# furballv3.net
KiCad netlist of a schematic drawn in EAGLE
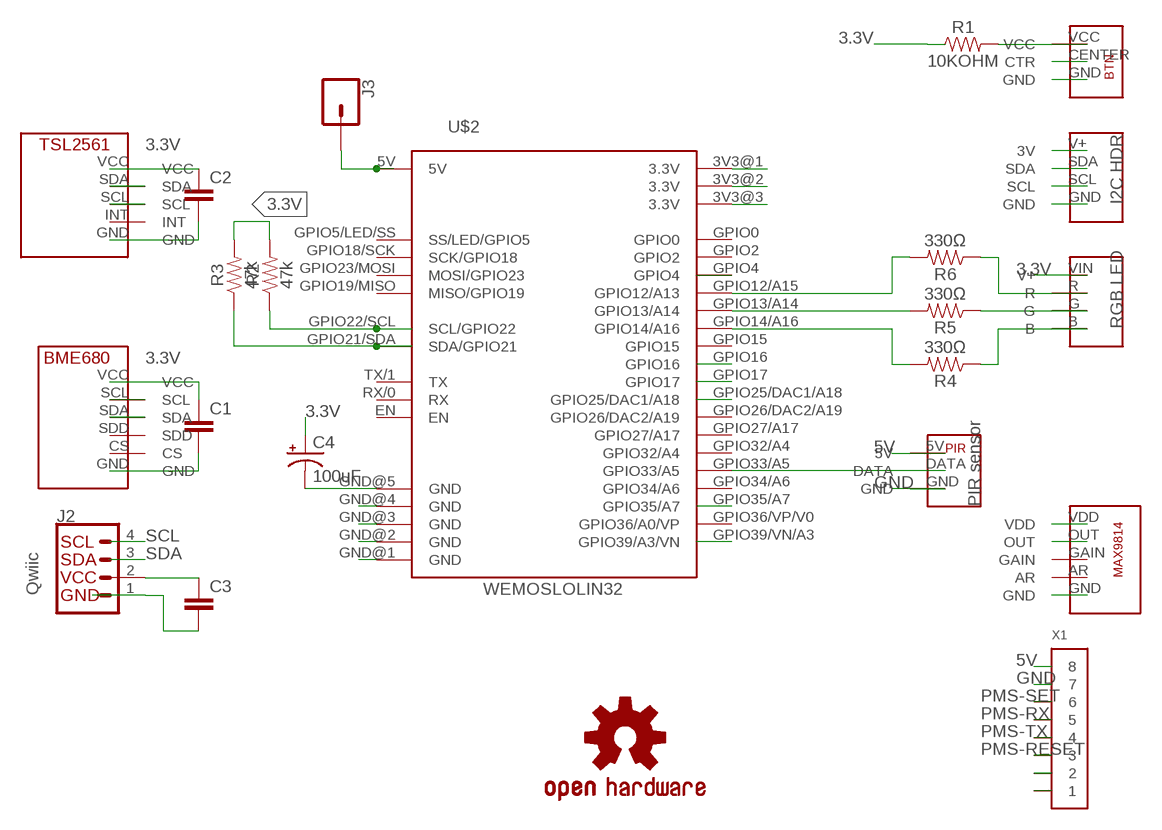
[diagram p0: schematic, sheet 1]

(export (version "E")
  (design (tool "Eeschema 10.0.6"))
  (components
    (comp (ref "C1")
      (value "10pF")
      (footprint "eagle-import:CAP-PTH-SMALL2")
      (libsource (lib "eagle-import") (part "CAPPTH2"))
    )
    (comp (ref "C2")
      (value "10pF")
      (footprint "eagle-import:CAP-PTH-SMALL2")
      (libsource (lib "eagle-import") (part "CAPPTH2"))
    )
    (comp (ref "C3")
      (value "10pF")
      (footprint "eagle-import:CAP-PTH-SMALL2")
      (libsource (lib "eagle-import") (part "CAPPTH2"))
    )
    (comp (ref "C4")
      (value "100uF")
      (footprint "eagle-import:CPOL-RADIAL-2.5MM-6.5MM")
      (libsource (lib "eagle-import") (part "100UF-POLAR-RADIAL-2.5MM-25V-20%"))
    )
    (comp (ref "J2")
      (value "QWIIC_CONNECTORJS-1MM")
      (footprint "eagle-import:1X04_1MM_RA")
      (libsource (lib "eagle-import") (part "QWIIC_CONNECTORJS-1MM"))
    )
    (comp (ref "J3")
      (value "CONN_01")
      (footprint "eagle-import:1X01")
      (libsource (lib "eagle-import") (part "CONN_01"))
    )
    (comp (ref "LOGO1")
      (value "OSHW-LOGOL")
      (footprint "eagle-import:OSHW-LOGO-L")
      (libsource (lib "eagle-import") (part "OSHW-LOGOL"))
    )
    (comp (ref "R1")
      (value "10KOHM")
      (footprint "eagle-import:AXIAL-0.3-KIT")
      (libsource (lib "eagle-import") (part "47KOHM"))
    )
    (comp (ref "R2")
      (value "47k")
      (footprint "eagle-import:AXIAL-0.3")
      (libsource (lib "eagle-import") (part "100KOHM-HORIZ-1/4W-1%"))
    )
    (comp (ref "R3")
      (value "47k")
      (footprint "eagle-import:AXIAL-0.3")
      (libsource (lib "eagle-import") (part "100KOHM-HORIZ-1/4W-1%"))
    )
    (comp (ref "R4")
      (value "330Ω")
      (footprint "eagle-import:AXIAL-0.3")
      (libsource (lib "eagle-import") (part "100KOHM-HORIZ-1/4W-1%"))
    )
    (comp (ref "R5")
      (value "330Ω")
      (footprint "eagle-import:AXIAL-0.3")
      (libsource (lib "eagle-import") (part "100KOHM-HORIZ-1/4W-1%"))
    )
    (comp (ref "R6")
      (value "330Ω")
      (footprint "eagle-import:AXIAL-0.3")
      (libsource (lib "eagle-import") (part "100KOHM-HORIZ-1/4W-1%"))
    )
    (comp (ref "U$1")
      (value "PIRHEADER")
      (footprint "eagle-import:PIRHEADER")
      (libsource (lib "eagle-import") (part "PIRHEADER"))
    )
    (comp (ref "U$2")
      (value "WEMOSLOLIN32")
      (footprint "eagle-import:LOLIN32VAR1")
      (libsource (lib "eagle-import") (part "WEMOSLOLIN32"))
    )
    (comp (ref "U$3")
      (value "BME680BREAKOUT")
      (footprint "eagle-import:BME680BREAKOUT")
      (libsource (lib "eagle-import") (part "BME680BREAKOUT"))
    )
    (comp (ref "U$4")
      (value "TSL2561BREAKOUT")
      (footprint "eagle-import:TSL2561BREAKOUT")
      (libsource (lib "eagle-import") (part "TSL2561BREAKOUT"))
    )
    (comp (ref "U$5")
      (value "RGBLEDHEADER")
      (footprint "eagle-import:RGBLEDHDR")
      (libsource (lib "eagle-import") (part "RGBLEDHEADER"))
    )
    (comp (ref "U$6")
      (value "I2CHEADER")
      (footprint "eagle-import:I2CHEADER")
      (libsource (lib "eagle-import") (part "I2CHEADER"))
    )
    (comp (ref "U$7")
      (value "MAX9814BREAKOUT")
      (footprint "eagle-import:MAX9814BREAKOUT")
      (libsource (lib "eagle-import") (part "MAX9814BREAKOUT"))
    )
    (comp (ref "U$8")
      (value "PUSHBUTTONHEADER")
      (footprint "eagle-import:PUSHBUTTONHEADER")
      (libsource (lib "eagle-import") (part "PUSHBUTTONHEADER"))
    )
    (comp (ref "X1")
      (value "CONN_8-1-53261")
      (footprint "eagle-import:PB-53261-08")
      (libsource (lib "eagle-import") (part "CONN_8-1-53261"))
    )
  )
  (nets
    (net (code "1") (name "/5V") (class "Default")
      (node (ref "J3") (pin "1") (pinfunction "1_1") (pintype "passive"))
      (node (ref "U$1") (pin "5V") (pinfunction "5V_5V") (pintype "power_in"))
      (node (ref "U$2") (pin "5V") (pinfunction "5V_5V") (pintype "power_in"))
      (node (ref "X1") (pin "8") (pinfunction "8_8") (pintype "bidirectional"))
    )
    (net (code "2") (name "/BUTTON") (class "Default")
      (node (ref "U$2") (pin "GPIO35/A7") (pinfunction "GPIO35/A7_GPIO35/A7") (pintype "bidirectional"))
      (node (ref "U$8") (pin "CENTER") (pinfunction "CTR_CENTER") (pintype "bidirectional"))
    )
    (net (code "3") (name "/GND") (class "Default")
      (node (ref "C1") (pin "2") (pinfunction "2_2") (pintype "passive"))
      (node (ref "C2") (pin "2") (pinfunction "2_2") (pintype "passive"))
      (node (ref "C3") (pin "2") (pinfunction "2_2") (pintype "passive"))
      (node (ref "C4") (pin "2") (pinfunction "-_2") (pintype "passive"))
      (node (ref "J2") (pin "1") (pinfunction "GND_1") (pintype "power_in"))
      (node (ref "U$1") (pin "GND") (pinfunction "GND_GND") (pintype "power_in"))
      (node (ref "U$2") (pin "GND@1") (pinfunction "GND_GND@1") (pintype "power_in"))
      (node (ref "U$2") (pin "GND@2") (pinfunction "GND_GND@2") (pintype "bidirectional"))
      (node (ref "U$2") (pin "GND@3") (pinfunction "GND_GND@3") (pintype "bidirectional"))
      (node (ref "U$2") (pin "GND@4") (pinfunction "GND_GND@4") (pintype "bidirectional"))
      (node (ref "U$2") (pin "GND@5") (pinfunction "GND_GND@5") (pintype "bidirectional"))
      (node (ref "U$3") (pin "GND") (pinfunction "GND_GND") (pintype "power_in"))
      (node (ref "U$4") (pin "GND") (pinfunction "GND_GND") (pintype "power_in"))
      (node (ref "U$6") (pin "GND") (pinfunction "GND_GND") (pintype "power_in"))
      (node (ref "U$7") (pin "GND") (pinfunction "GND_GND") (pintype "power_in"))
      (node (ref "U$8") (pin "GND") (pinfunction "GND_GND") (pintype "power_in"))
      (node (ref "X1") (pin "7") (pinfunction "7_7") (pintype "bidirectional"))
    )
    (net (code "4") (name "/PMS-RESET") (class "Default")
      (node (ref "U$2") (pin "GPIO25/DAC1/A18") (pinfunction "GPIO25/DAC1/A18_GPIO25/DAC1/A18") (pintype "bidirectional"))
      (node (ref "X1") (pin "3") (pinfunction "3_3") (pintype "bidirectional"))
    )
    (net (code "5") (name "/PMS-RX") (class "Default")
      (node (ref "U$2") (pin "GPIO16") (pinfunction "GPIO16_GPIO16") (pintype "bidirectional"))
      (node (ref "X1") (pin "5") (pinfunction "5_5") (pintype "bidirectional"))
    )
    (net (code "6") (name "/PMS-SET") (class "Default")
      (node (ref "U$2") (pin "GPIO4") (pinfunction "GPIO4_GPIO4") (pintype "bidirectional"))
      (node (ref "X1") (pin "6") (pinfunction "6_6") (pintype "bidirectional"))
    )
    (net (code "7") (name "/PMS-TX") (class "Default")
      (node (ref "U$2") (pin "GPIO17") (pinfunction "GPIO17_GPIO17") (pintype "bidirectional"))
      (node (ref "X1") (pin "4") (pinfunction "4_4") (pintype "bidirectional"))
    )
    (net (code "8") (name "/SCL") (class "Default")
      (node (ref "J2") (pin "4") (pinfunction "SCL_4") (pintype "passive"))
      (node (ref "R2") (pin "P$1") (pinfunction "1_P$1") (pintype "passive"))
      (node (ref "U$2") (pin "GPIO22/SCL") (pinfunction "SCL/GPIO22_GPIO22/SCL") (pintype "bidirectional"))
      (node (ref "U$3") (pin "SCL") (pinfunction "SCL_SCL") (pintype "bidirectional"))
      (node (ref "U$4") (pin "SCL") (pinfunction "SCL_SCL") (pintype "bidirectional"))
      (node (ref "U$6") (pin "SCL") (pinfunction "SCL_SCL") (pintype "bidirectional"))
    )
    (net (code "9") (name "/SDA") (class "Default")
      (node (ref "J2") (pin "3") (pinfunction "SDA_3") (pintype "passive"))
      (node (ref "R3") (pin "P$1") (pinfunction "1_P$1") (pintype "passive"))
      (node (ref "U$2") (pin "GPIO21/SDA") (pinfunction "SDA/GPIO21_GPIO21/SDA") (pintype "bidirectional"))
      (node (ref "U$3") (pin "SDA") (pinfunction "SDA_SDA") (pintype "bidirectional"))
      (node (ref "U$4") (pin "SDA") (pinfunction "SDA_SDA") (pintype "bidirectional"))
      (node (ref "U$6") (pin "SDA") (pinfunction "SDA_SDA") (pintype "bidirectional"))
    )
    (net (code "10") (name "/SOUND") (class "Default")
      (node (ref "U$2") (pin "GPIO39/VN/A3") (pinfunction "GPIO39/A3/VN_GPIO39/VN/A3") (pintype "bidirectional"))
      (node (ref "U$7") (pin "OUT") (pinfunction "OUT_OUT") (pintype "output"))
    )
    (net (code "11") (name "3.3V") (class "Default")
      (node (ref "C1") (pin "1") (pinfunction "1_1") (pintype "passive"))
      (node (ref "C2") (pin "1") (pinfunction "1_1") (pintype "passive"))
      (node (ref "C3") (pin "1") (pinfunction "1_1") (pintype "passive"))
      (node (ref "C4") (pin "1") (pinfunction "+_1") (pintype "passive"))
      (node (ref "J2") (pin "2") (pinfunction "VCC_2") (pintype "power_in"))
      (node (ref "R1") (pin "P$1") (pinfunction "1_P$1") (pintype "passive"))
      (node (ref "R2") (pin "P$2") (pinfunction "2_P$2") (pintype "passive"))
      (node (ref "R3") (pin "P$2") (pinfunction "2_P$2") (pintype "passive"))
      (node (ref "U$2") (pin "3V3@1") (pinfunction "3.3V_3V3@1") (pintype "bidirectional"))
      (node (ref "U$2") (pin "3V3@2") (pinfunction "3.3V_3V3@2") (pintype "bidirectional"))
      (node (ref "U$2") (pin "3V3@3") (pinfunction "3.3V_3V3@3") (pintype "power_in"))
      (node (ref "U$3") (pin "VCC") (pinfunction "VCC_VCC") (pintype "power_in"))
      (node (ref "U$4") (pin "VCC") (pinfunction "VCC_VCC") (pintype "power_in"))
      (node (ref "U$5") (pin "VIN") (pinfunction "V+_VIN") (pintype "power_in"))
      (node (ref "U$6") (pin "V+") (pinfunction "3V_V+") (pintype "power_in"))
      (node (ref "U$7") (pin "VDD") (pinfunction "VDD_VDD") (pintype "power_in"))
    )
    (net (code "12") (name "Net-(R1-2)") (class "Default")
      (node (ref "R1") (pin "P$2") (pinfunction "2_P$2") (pintype "passive"))
      (node (ref "U$8") (pin "VCC") (pinfunction "VCC_VCC") (pintype "bidirectional"))
    )
    (net (code "13") (name "Net-(R4-1)") (class "Default")
      (node (ref "R4") (pin "P$1") (pinfunction "1_P$1") (pintype "passive"))
      (node (ref "U$5") (pin "B") (pinfunction "B_B") (pintype "input"))
    )
    (net (code "14") (name "Net-(R4-2)") (class "Default")
      (node (ref "R4") (pin "P$2") (pinfunction "2_P$2") (pintype "passive"))
      (node (ref "U$2") (pin "GPIO14/A16") (pinfunction "GPIO14/A16_GPIO14/A16") (pintype "bidirectional"))
    )
    (net (code "15") (name "Net-(R5-1)") (class "Default")
      (node (ref "R5") (pin "P$1") (pinfunction "1_P$1") (pintype "passive"))
      (node (ref "U$5") (pin "G") (pinfunction "G_G") (pintype "input"))
    )
    (net (code "16") (name "Net-(R5-2)") (class "Default")
      (node (ref "R5") (pin "P$2") (pinfunction "2_P$2") (pintype "passive"))
      (node (ref "U$2") (pin "GPIO13/A14") (pinfunction "GPIO13/A14_GPIO13/A14") (pintype "bidirectional"))
    )
    (net (code "17") (name "Net-(R6-1)") (class "Default")
      (node (ref "R6") (pin "P$1") (pinfunction "1_P$1") (pintype "passive"))
      (node (ref "U$5") (pin "R") (pinfunction "R_R") (pintype "input"))
    )
    (net (code "18") (name "Net-(R6-2)") (class "Default")
      (node (ref "R6") (pin "P$2") (pinfunction "2_P$2") (pintype "passive"))
      (node (ref "U$2") (pin "GPIO12/A15") (pinfunction "GPIO12/A13_GPIO12/A15") (pintype "bidirectional"))
    )
    (net (code "19") (name "Net-(U$1-PadDATA)") (class "Default")
      (node (ref "U$1") (pin "DATA") (pinfunction "DATA_DATA") (pintype "output"))
      (node (ref "U$2") (pin "GPIO33/A5") (pinfunction "GPIO33/A5_GPIO33/A5") (pintype "bidirectional"))
    )
    (net (code "20") (name "unconnected-(U$2-GPIO36{slash}A0{slash}VP-PadGPIO36{slash}VP{slash}V0)") (class "Default")
      (node (ref "U$2") (pin "GPIO36/VP/V0") (pinfunction "GPIO36/A0/VP_GPIO36/VP/V0") (pintype "bidirectional"))
    )
    (net (code "21") (name "unconnected-(U$2-MISO{slash}GPIO19-PadGPIO19{slash}MISO)") (class "Default")
      (node (ref "U$2") (pin "GPIO19/MISO") (pinfunction "MISO/GPIO19_GPIO19/MISO") (pintype "bidirectional"))
    )
    (net (code "22") (name "unconnected-(U$2-MOSI{slash}GPIO23-PadGPIO23{slash}MOSI)") (class "Default")
      (node (ref "U$2") (pin "GPIO23/MOSI") (pinfunction "MOSI/GPIO23_GPIO23/MOSI") (pintype "bidirectional"))
    )
    (net (code "23") (name "unconnected-(U$2-PadEN)") (class "Default")
      (node (ref "U$2") (pin "EN") (pinfunction "EN_EN") (pintype "bidirectional"))
    )
    (net (code "24") (name "unconnected-(U$2-PadGPIO0)") (class "Default")
      (node (ref "U$2") (pin "GPIO0") (pinfunction "GPIO0_GPIO0") (pintype "bidirectional"))
    )
    (net (code "25") (name "unconnected-(U$2-PadGPIO2)") (class "Default")
      (node (ref "U$2") (pin "GPIO2") (pinfunction "GPIO2_GPIO2") (pintype "bidirectional"))
    )
    (net (code "26") (name "unconnected-(U$2-PadGPIO15)") (class "Default")
      (node (ref "U$2") (pin "GPIO15") (pinfunction "GPIO15_GPIO15") (pintype "bidirectional"))
    )
    (net (code "27") (name "unconnected-(U$2-PadGPIO26{slash}DAC2{slash}A19)") (class "Default")
      (node (ref "U$2") (pin "GPIO26/DAC2/A19") (pinfunction "GPIO26/DAC2/A19_GPIO26/DAC2/A19") (pintype "bidirectional"))
    )
    (net (code "28") (name "unconnected-(U$2-PadGPIO27{slash}A17)") (class "Default")
      (node (ref "U$2") (pin "GPIO27/A17") (pinfunction "GPIO27/A17_GPIO27/A17") (pintype "bidirectional"))
    )
    (net (code "29") (name "unconnected-(U$2-PadGPIO32{slash}A4)") (class "Default")
      (node (ref "U$2") (pin "GPIO32/A4") (pinfunction "GPIO32/A4_GPIO32/A4") (pintype "bidirectional"))
    )
    (net (code "30") (name "unconnected-(U$2-PadGPIO34{slash}A6)") (class "Default")
      (node (ref "U$2") (pin "GPIO34/A6") (pinfunction "GPIO34/A6_GPIO34/A6") (pintype "bidirectional"))
    )
    (net (code "31") (name "unconnected-(U$2-RX-PadRX{slash}0)") (class "Default")
      (node (ref "U$2") (pin "RX/0") (pinfunction "RX_RX/0") (pintype "input"))
    )
    (net (code "32") (name "unconnected-(U$2-SCK{slash}GPIO18-PadGPIO18{slash}SCK)") (class "Default")
      (node (ref "U$2") (pin "GPIO18/SCK") (pinfunction "SCK/GPIO18_GPIO18/SCK") (pintype "bidirectional"))
    )
    (net (code "33") (name "unconnected-(U$2-SS{slash}LED{slash}GPIO5-PadGPIO5{slash}LED{slash}SS)") (class "Default")
      (node (ref "U$2") (pin "GPIO5/LED/SS") (pinfunction "SS/LED/GPIO5_GPIO5/LED/SS") (pintype "bidirectional"))
    )
    (net (code "34") (name "unconnected-(U$2-TX-PadTX{slash}1)") (class "Default")
      (node (ref "U$2") (pin "TX/1") (pinfunction "TX_TX/1") (pintype "output"))
    )
    (net (code "35") (name "unconnected-(U$3-PadCS)") (class "Default")
      (node (ref "U$3") (pin "CS") (pinfunction "CS_CS") (pintype "bidirectional"))
    )
    (net (code "36") (name "unconnected-(U$3-PadSDD)") (class "Default")
      (node (ref "U$3") (pin "SDD") (pinfunction "SDD_SDD") (pintype "bidirectional"))
    )
    (net (code "37") (name "unconnected-(U$4-PadINT)") (class "Default")
      (node (ref "U$4") (pin "INT") (pinfunction "INT_INT") (pintype "output"))
    )
    (net (code "38") (name "unconnected-(U$7-PadAR)") (class "Default")
      (node (ref "U$7") (pin "AR") (pinfunction "AR_AR") (pintype "input"))
    )
    (net (code "39") (name "unconnected-(U$7-PadGAIN)") (class "Default")
      (node (ref "U$7") (pin "GAIN") (pinfunction "GAIN_GAIN") (pintype "input"))
    )
    (net (code "40") (name "unconnected-(X1-Pad1)") (class "Default")
      (node (ref "X1") (pin "1") (pinfunction "1_1") (pintype "bidirectional"))
    )
    (net (code "41") (name "unconnected-(X1-Pad2)") (class "Default")
      (node (ref "X1") (pin "2") (pinfunction "2_2") (pintype "bidirectional"))
    )
  )
)
